# PCB_LC_LPF_T.net
KiCad netlist of a schematic drawn in Altium Designer
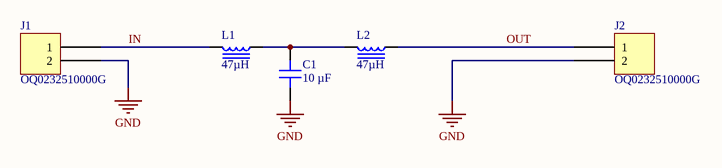
[diagram p0: PCB_LC_LPF_T.SchDoc]

(export (version "E")
  (design (tool "Eeschema 10.0.6"))
  (components
    (comp (ref "C1")
      (value "10 µF")
      (footprint "CAP 0603_1608")
      (description "CAP CER 10UF 10V X5R 0603")
      (fields
        (field (name "PART NUMBER") "MD0603BW106M100NHT-EM")
        (field (name "MANUFACTURER") "Knowles Novacap")
      )
      (libsource (lib "Celestial Altium Library - altium_library") (part "Capacitor"))
    )
    (comp (ref "J1")
      (value "OQ0232510000G")
      (footprint "FCI 06-381-2PIN")
      (description "TERM BLOCK HDR 2POS 90DEG 3.81MM")
      (fields (field (name "MANUFACTURER") "Amphenol Anytek"))
      (libsource (lib "Celestial Altium Library - altium_library") (part "2 Pin"))
    )
    (comp (ref "J2")
      (value "OQ0232510000G")
      (footprint "FCI 06-381-2PIN")
      (description "TERM BLOCK HDR 2POS 90DEG 3.81MM")
      (fields (field (name "MANUFACTURER") "Amphenol Anytek"))
      (libsource (lib "") (part "2 Pin_1"))
    )
    (comp (ref "L1")
      (value "47µH")
      (footprint "IND 0603_1608 RF WW")
      (description "INDUCTORPOWER LINE 0603 47H 20%")
      (fields (field (name "PART NUMBER") "L0603B470MPWFT") (field (name "MANUFACTURER") "KEMET"))
      (libsource (lib "Celestial Altium Library - altium_library") (part "Inductor"))
    )
    (comp (ref "L2")
      (value "47µH")
      (footprint "IND 0603_1608 RF WW")
      (description "INDUCTORPOWER LINE 0603 47H 20%")
      (fields (field (name "PART NUMBER") "L0603B470MPWFT") (field (name "MANUFACTURER") "KEMET"))
      (libsource (lib "Celestial Altium Library - altium_library") (part "Inductor"))
    )
  )
  (nets
    (net (code "1") (name "/IN") (class "Default")
      (node (ref "J1") (pin "1") (pinfunction "1_1") (pintype "passive"))
      (node (ref "L1") (pin "2") (pinfunction "2_2") (pintype "passive"))
    )
    (net (code "2") (name "/OUT") (class "Default")
      (node (ref "J2") (pin "1") (pinfunction "1_1") (pintype "passive"))
      (node (ref "L2") (pin "1") (pinfunction "1_1") (pintype "passive"))
    )
    (net (code "3") (name "GND") (class "Default")
      (node (ref "C1") (pin "1") (pinfunction "1_1") (pintype "passive"))
      (node (ref "J1") (pin "2") (pinfunction "2_2") (pintype "passive"))
      (node (ref "J2") (pin "2") (pinfunction "2_2") (pintype "passive"))
    )
    (net (code "4") (name "Net-(C1-Pad2)") (class "Default")
      (node (ref "C1") (pin "2") (pinfunction "2_2") (pintype "passive"))
      (node (ref "L1") (pin "1") (pinfunction "1_1") (pintype "passive"))
      (node (ref "L2") (pin "2") (pinfunction "2_2") (pintype "passive"))
    )
  )
)
